# emg-ps-usb.net
KiCad netlist of a schematic drawn in EAGLE
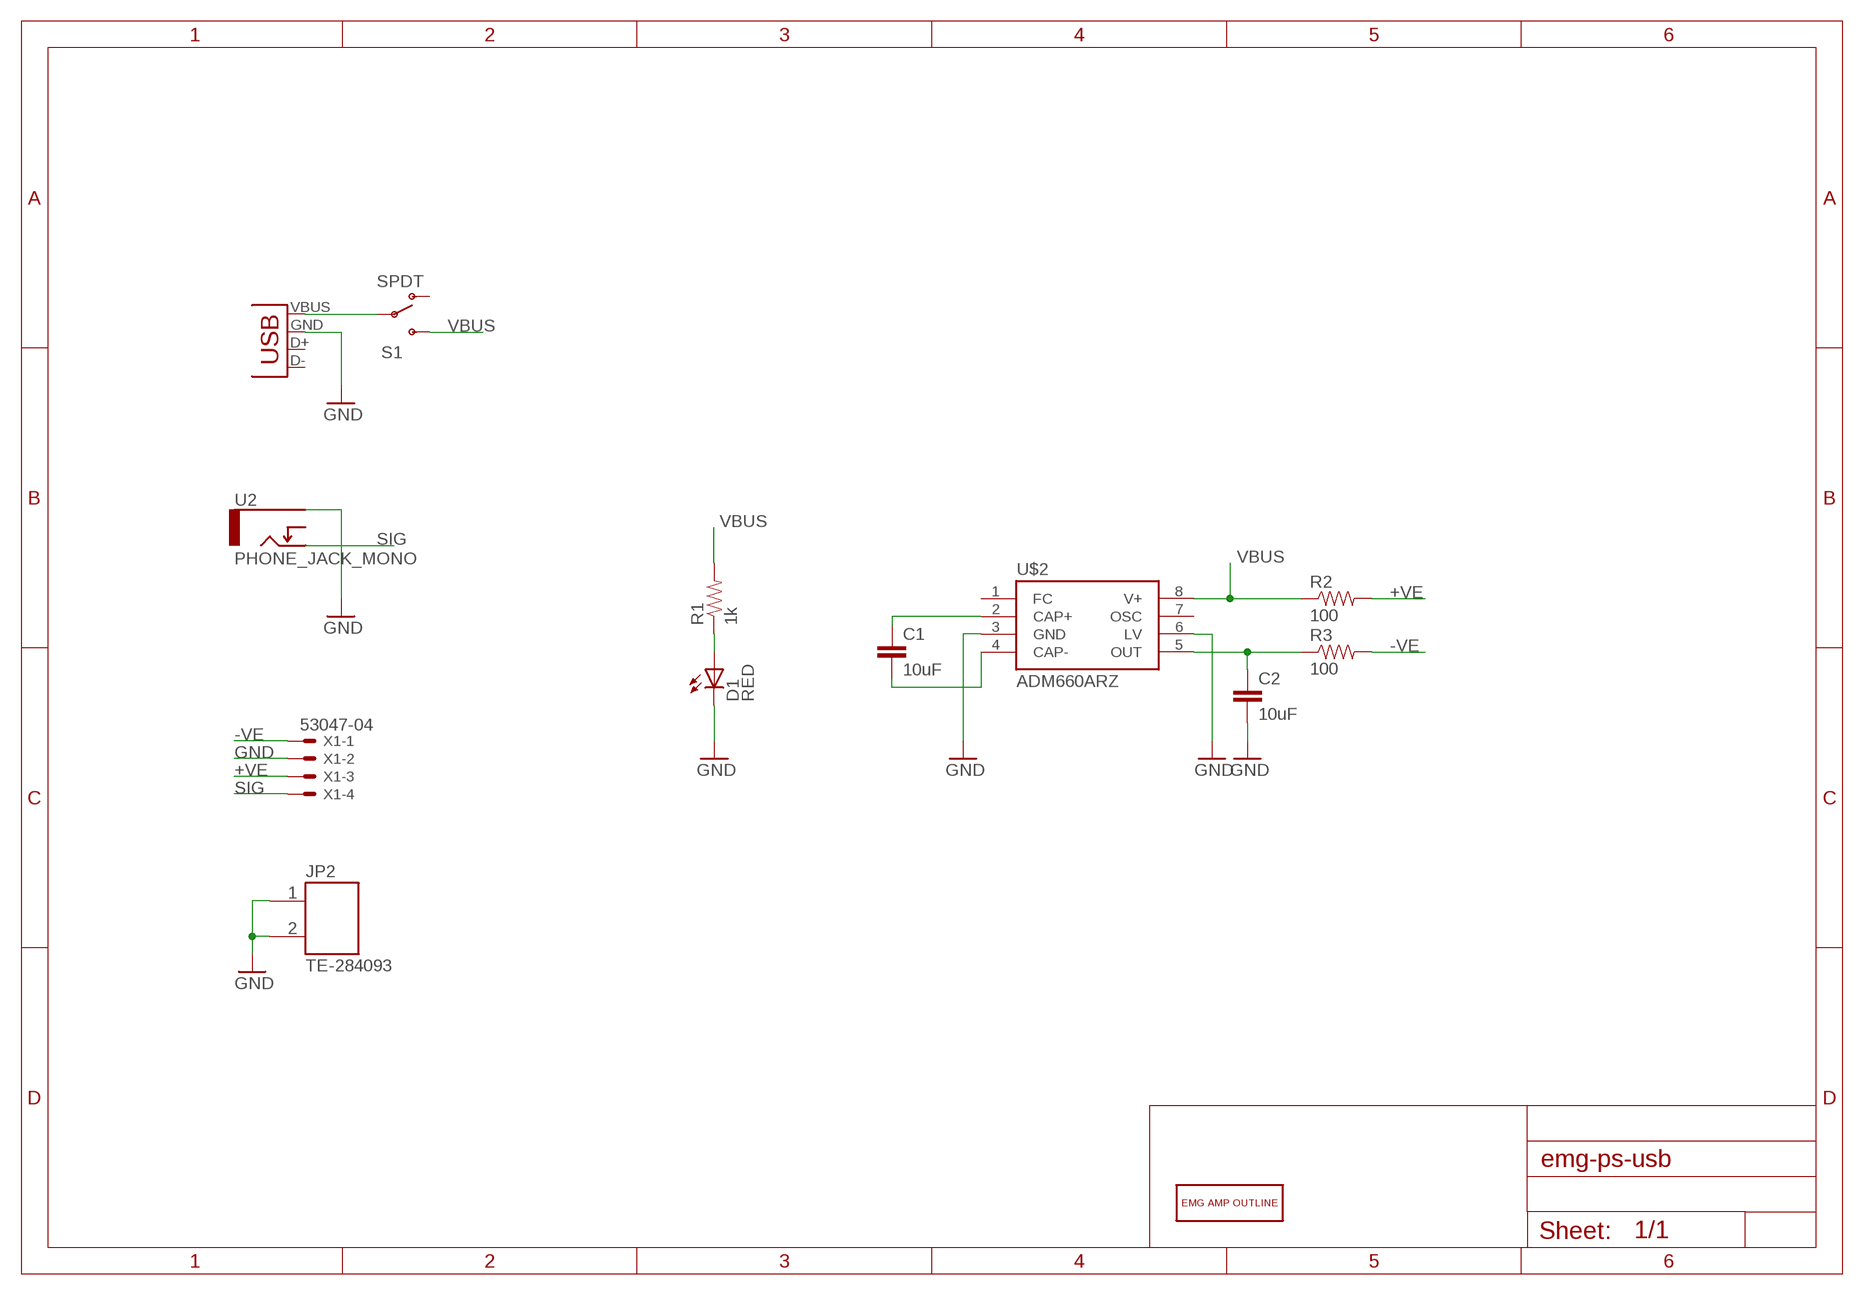
[diagram p0: schematic, sheet 1]

(export (version "E")
  (design (tool "Eeschema 10.0.6"))
  (components
    (comp (ref "C1")
      (value "10uF")
      (footprint "eagle-import:0805")
      (libsource (lib "eagle-import") (part "CAP0805"))
    )
    (comp (ref "C2")
      (value "10uF")
      (footprint "eagle-import:0805")
      (libsource (lib "eagle-import") (part "CAP0805"))
    )
    (comp (ref "D1")
      (value "RED")
      (footprint "eagle-import:LED-0603")
      (libsource (lib "eagle-import") (part "LED-RED0603"))
    )
    (comp (ref "JP1")
      (value "USB-A-H")
      (footprint "eagle-import:USB-A-H")
      (libsource (lib "eagle-import") (part "USB-A-H"))
    )
    (comp (ref "JP2")
      (value "TE-284093")
      (footprint "eagle-import:TE-284093")
      (libsource (lib "eagle-import") (part "TE-284093"))
    )
    (comp (ref "R1")
      (value "1k")
      (footprint "eagle-import:0805")
      (libsource (lib "eagle-import") (part "RESISTOR0805-RES"))
    )
    (comp (ref "R2")
      (value "100")
      (footprint "eagle-import:0805")
      (libsource (lib "eagle-import") (part "RESISTOR0805-RES"))
    )
    (comp (ref "R3")
      (value "100")
      (footprint "eagle-import:0805")
      (libsource (lib "eagle-import") (part "RESISTOR0805-RES"))
    )
    (comp (ref "S1")
      (value "SPDT")
      (footprint "eagle-import:SWITCH-SPST-SMD-A")
      (libsource (lib "eagle-import") (part "SWITCH-SPDT-SMD-A"))
    )
    (comp (ref "U$2")
      (value "ADM660ARZ")
      (footprint "eagle-import:SOIC8")
      (libsource (lib "eagle-import") (part "ADM660ARZ"))
    )
    (comp (ref "U$3")
      (value "EMG_AMP_OUTLINE-Y03ENDS")
      (footprint "eagle-import:EMG_Y03_OUTLINEENDS")
      (libsource (lib "eagle-import") (part "EMG_AMP_OUTLINE-Y03ENDS"))
    )
    (comp (ref "U2")
      (value "PHONE_JACK_MONO")
      (footprint "eagle-import:MJ-3523-SMT")
      (libsource (lib "eagle-import") (part "PHONE_JACK_MONO"))
    )
    (comp (ref "X1")
      (value "53047-04")
      (footprint "eagle-import:53047-04")
      (fields (field (name "MF") "WALDOM/MOLEX") (field (name "MPN") "53047-0410"))
      (libsource (lib "eagle-import") (part "53?-04047"))
    )
  )
  (nets
    (net (code "1") (name "/+VE") (class "Default")
      (node (ref "R2") (pin "2") (pinfunction "2_2") (pintype "passive"))
      (node (ref "X1") (pin "3") (pinfunction "S_3") (pintype "passive"))
    )
    (net (code "2") (name "/-VE") (class "Default")
      (node (ref "R3") (pin "2") (pinfunction "2_2") (pintype "passive"))
      (node (ref "X1") (pin "1") (pinfunction "S_1") (pintype "passive"))
    )
    (net (code "3") (name "/SIG") (class "Default")
      (node (ref "U2") (pin "P$2") (pinfunction "P$2_P$2") (pintype "bidirectional"))
      (node (ref "X1") (pin "4") (pinfunction "S_4") (pintype "passive"))
    )
    (net (code "4") (name "/VBUS") (class "Default")
      (node (ref "R1") (pin "2") (pinfunction "2_2") (pintype "passive"))
      (node (ref "R2") (pin "1") (pinfunction "1_1") (pintype "passive"))
      (node (ref "S1") (pin "3") (pinfunction "S_3") (pintype "passive"))
      (node (ref "U$2") (pin "8") (pinfunction "V+_8") (pintype "bidirectional"))
    )
    (net (code "5") (name "GND") (class "Default")
      (node (ref "C2") (pin "2") (pinfunction "2_2") (pintype "passive"))
      (node (ref "D1") (pin "C") (pinfunction "C_C") (pintype "passive"))
      (node (ref "JP1") (pin "GND") (pinfunction "VBUS_GND") (pintype "bidirectional"))
      (node (ref "JP2") (pin "P$1") (pinfunction "1_P$1") (pintype "bidirectional"))
      (node (ref "JP2") (pin "P$2") (pinfunction "2_P$2") (pintype "bidirectional"))
      (node (ref "U$2") (pin "3") (pinfunction "GND_3") (pintype "bidirectional"))
      (node (ref "U$2") (pin "6") (pinfunction "LV_6") (pintype "bidirectional"))
      (node (ref "U2") (pin "P$1") (pinfunction "P$1_P$1") (pintype "bidirectional"))
      (node (ref "X1") (pin "2") (pinfunction "S_2") (pintype "passive"))
    )
    (net (code "6") (name "Net-(D1-PadA)") (class "Default")
      (node (ref "D1") (pin "A") (pinfunction "A_A") (pintype "passive"))
      (node (ref "R1") (pin "1") (pinfunction "1_1") (pintype "passive"))
    )
    (net (code "7") (name "Net-(JP1-GND)") (class "Default")
      (node (ref "JP1") (pin "VBUS") (pinfunction "GND_VBUS") (pintype "bidirectional"))
      (node (ref "S1") (pin "2") (pinfunction "P_2") (pintype "passive"))
    )
    (net (code "8") (name "Net-(U$2-CAP+)") (class "Default")
      (node (ref "C1") (pin "1") (pinfunction "1_1") (pintype "passive"))
      (node (ref "U$2") (pin "2") (pinfunction "CAP+_2") (pintype "bidirectional"))
    )
    (net (code "9") (name "Net-(U$2-CAP-)") (class "Default")
      (node (ref "C1") (pin "2") (pinfunction "2_2") (pintype "passive"))
      (node (ref "U$2") (pin "4") (pinfunction "CAP-_4") (pintype "bidirectional"))
    )
    (net (code "10") (name "Net-(U$2-OUT)") (class "Default")
      (node (ref "C2") (pin "1") (pinfunction "1_1") (pintype "passive"))
      (node (ref "R3") (pin "1") (pinfunction "1_1") (pintype "passive"))
      (node (ref "U$2") (pin "5") (pinfunction "OUT_5") (pintype "bidirectional"))
    )
    (net (code "11") (name "unconnected-(JP1-D+-PadD-)") (class "Default")
      (node (ref "JP1") (pin "D-") (pinfunction "D+_D-") (pintype "bidirectional"))
    )
    (net (code "12") (name "unconnected-(JP1-D--PadD+)") (class "Default")
      (node (ref "JP1") (pin "D+") (pinfunction "D-_D+") (pintype "bidirectional"))
    )
    (net (code "13") (name "unconnected-(S1-O-Pad1)") (class "Default")
      (node (ref "S1") (pin "1") (pinfunction "O_1") (pintype "passive"))
    )
    (net (code "14") (name "unconnected-(U$2-FC-Pad1)") (class "Default")
      (node (ref "U$2") (pin "1") (pinfunction "FC_1") (pintype "bidirectional"))
    )
    (net (code "15") (name "unconnected-(U$2-OSC-Pad7)") (class "Default")
      (node (ref "U$2") (pin "7") (pinfunction "OSC_7") (pintype "bidirectional"))
    )
    (net (code "16") (name "unconnected-(U2-PadP$3)") (class "Default")
      (node (ref "U2") (pin "P$3") (pinfunction "P$3_P$3") (pintype "bidirectional"))
    )
  )
)
